# servo_headers.net
KiCad netlist of a schematic drawn in Altium Designer
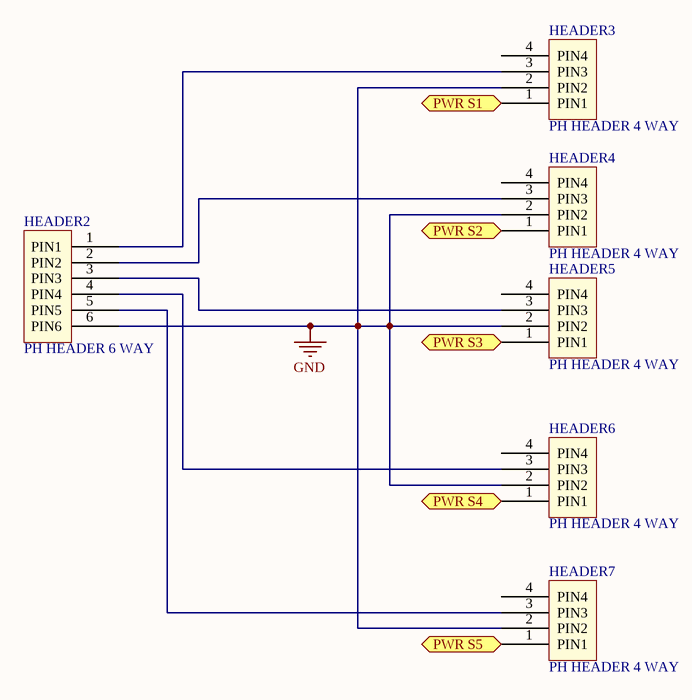
[diagram p0: servo_headers.SchDoc]

(export (version "E")
  (design (tool "Eeschema 10.0.6"))
  (components
    (comp (ref "HEADER2")
      (value "PH HEADER 6 WAY")
      (footprint "PH CONNECTOR 6 WAY")
      (libsource (lib "PH_HEADER_6_WAY") (part "PH HEADER 6 WAY"))
    )
    (comp (ref "HEADER3")
      (value "PH HEADER 4 WAY")
      (footprint "PH_HEADER 4WAY")
      (libsource (lib "PH_HEADER_4_WAY") (part "PH HEADER 4 WAY"))
    )
    (comp (ref "HEADER4")
      (value "PH HEADER 4 WAY")
      (footprint "PH_HEADER 4WAY")
      (libsource (lib "PH_HEADER_4_WAY") (part "PH HEADER 4 WAY"))
    )
    (comp (ref "HEADER5")
      (value "PH HEADER 4 WAY")
      (footprint "PH_HEADER 4WAY")
      (libsource (lib "PH_HEADER_4_WAY") (part "PH HEADER 4 WAY"))
    )
    (comp (ref "HEADER6")
      (value "PH HEADER 4 WAY")
      (footprint "PH_HEADER 4WAY")
      (libsource (lib "PH_HEADER_4_WAY") (part "PH HEADER 4 WAY"))
    )
    (comp (ref "HEADER7")
      (value "PH HEADER 4 WAY")
      (footprint "PH_HEADER 4WAY")
      (libsource (lib "PH_HEADER_4_WAY") (part "PH HEADER 4 WAY"))
    )
  )
  (nets
    (net (code "1") (name "/PWR S1") (class "Default")
      (node (ref "HEADER3") (pin "1") (pinfunction "PIN1_1") (pintype "passive"))
    )
    (net (code "2") (name "/PWR S2") (class "Default")
      (node (ref "HEADER4") (pin "1") (pinfunction "PIN1_1") (pintype "passive"))
    )
    (net (code "3") (name "/PWR S3") (class "Default")
      (node (ref "HEADER5") (pin "1") (pinfunction "PIN1_1") (pintype "passive"))
    )
    (net (code "4") (name "/PWR S4") (class "Default")
      (node (ref "HEADER6") (pin "1") (pinfunction "PIN1_1") (pintype "passive"))
    )
    (net (code "5") (name "/PWR S5") (class "Default")
      (node (ref "HEADER7") (pin "1") (pinfunction "PIN1_1") (pintype "passive"))
    )
    (net (code "6") (name "GND") (class "Default")
      (node (ref "HEADER2") (pin "6") (pinfunction "PIN6_6") (pintype "passive"))
      (node (ref "HEADER3") (pin "2") (pinfunction "PIN2_2") (pintype "passive"))
      (node (ref "HEADER4") (pin "2") (pinfunction "PIN2_2") (pintype "passive"))
      (node (ref "HEADER5") (pin "2") (pinfunction "PIN2_2") (pintype "passive"))
      (node (ref "HEADER6") (pin "2") (pinfunction "PIN2_2") (pintype "passive"))
      (node (ref "HEADER7") (pin "2") (pinfunction "PIN2_2") (pintype "passive"))
    )
    (net (code "7") (name "Net-(HEADER2-PIN1)") (class "Default")
      (node (ref "HEADER2") (pin "1") (pinfunction "PIN1_1") (pintype "passive"))
      (node (ref "HEADER3") (pin "3") (pinfunction "PIN3_3") (pintype "passive"))
    )
    (net (code "8") (name "Net-(HEADER2-PIN2)") (class "Default")
      (node (ref "HEADER2") (pin "2") (pinfunction "PIN2_2") (pintype "passive"))
      (node (ref "HEADER4") (pin "3") (pinfunction "PIN3_3") (pintype "passive"))
    )
    (net (code "9") (name "Net-(HEADER2-PIN3)") (class "Default")
      (node (ref "HEADER2") (pin "3") (pinfunction "PIN3_3") (pintype "passive"))
      (node (ref "HEADER5") (pin "3") (pinfunction "PIN3_3") (pintype "passive"))
    )
    (net (code "10") (name "Net-(HEADER2-PIN4)") (class "Default")
      (node (ref "HEADER2") (pin "4") (pinfunction "PIN4_4") (pintype "passive"))
      (node (ref "HEADER6") (pin "3") (pinfunction "PIN3_3") (pintype "passive"))
    )
    (net (code "11") (name "Net-(HEADER2-PIN5)") (class "Default")
      (node (ref "HEADER2") (pin "5") (pinfunction "PIN5_5") (pintype "passive"))
      (node (ref "HEADER7") (pin "3") (pinfunction "PIN3_3") (pintype "passive"))
    )
    (net (code "12") (name "unconnected-(HEADER3-PIN4-Pad4)") (class "Default")
      (node (ref "HEADER3") (pin "4") (pinfunction "PIN4_4") (pintype "passive"))
    )
    (net (code "13") (name "unconnected-(HEADER4-PIN4-Pad4)") (class "Default")
      (node (ref "HEADER4") (pin "4") (pinfunction "PIN4_4") (pintype "passive"))
    )
    (net (code "14") (name "unconnected-(HEADER5-PIN4-Pad4)") (class "Default")
      (node (ref "HEADER5") (pin "4") (pinfunction "PIN4_4") (pintype "passive"))
    )
    (net (code "15") (name "unconnected-(HEADER6-PIN4-Pad4)") (class "Default")
      (node (ref "HEADER6") (pin "4") (pinfunction "PIN4_4") (pintype "passive"))
    )
    (net (code "16") (name "unconnected-(HEADER7-PIN4-Pad4)") (class "Default")
      (node (ref "HEADER7") (pin "4") (pinfunction "PIN4_4") (pintype "passive"))
    )
  )
)
